# main.net
KiCad netlist of a schematic drawn in Altium Designer
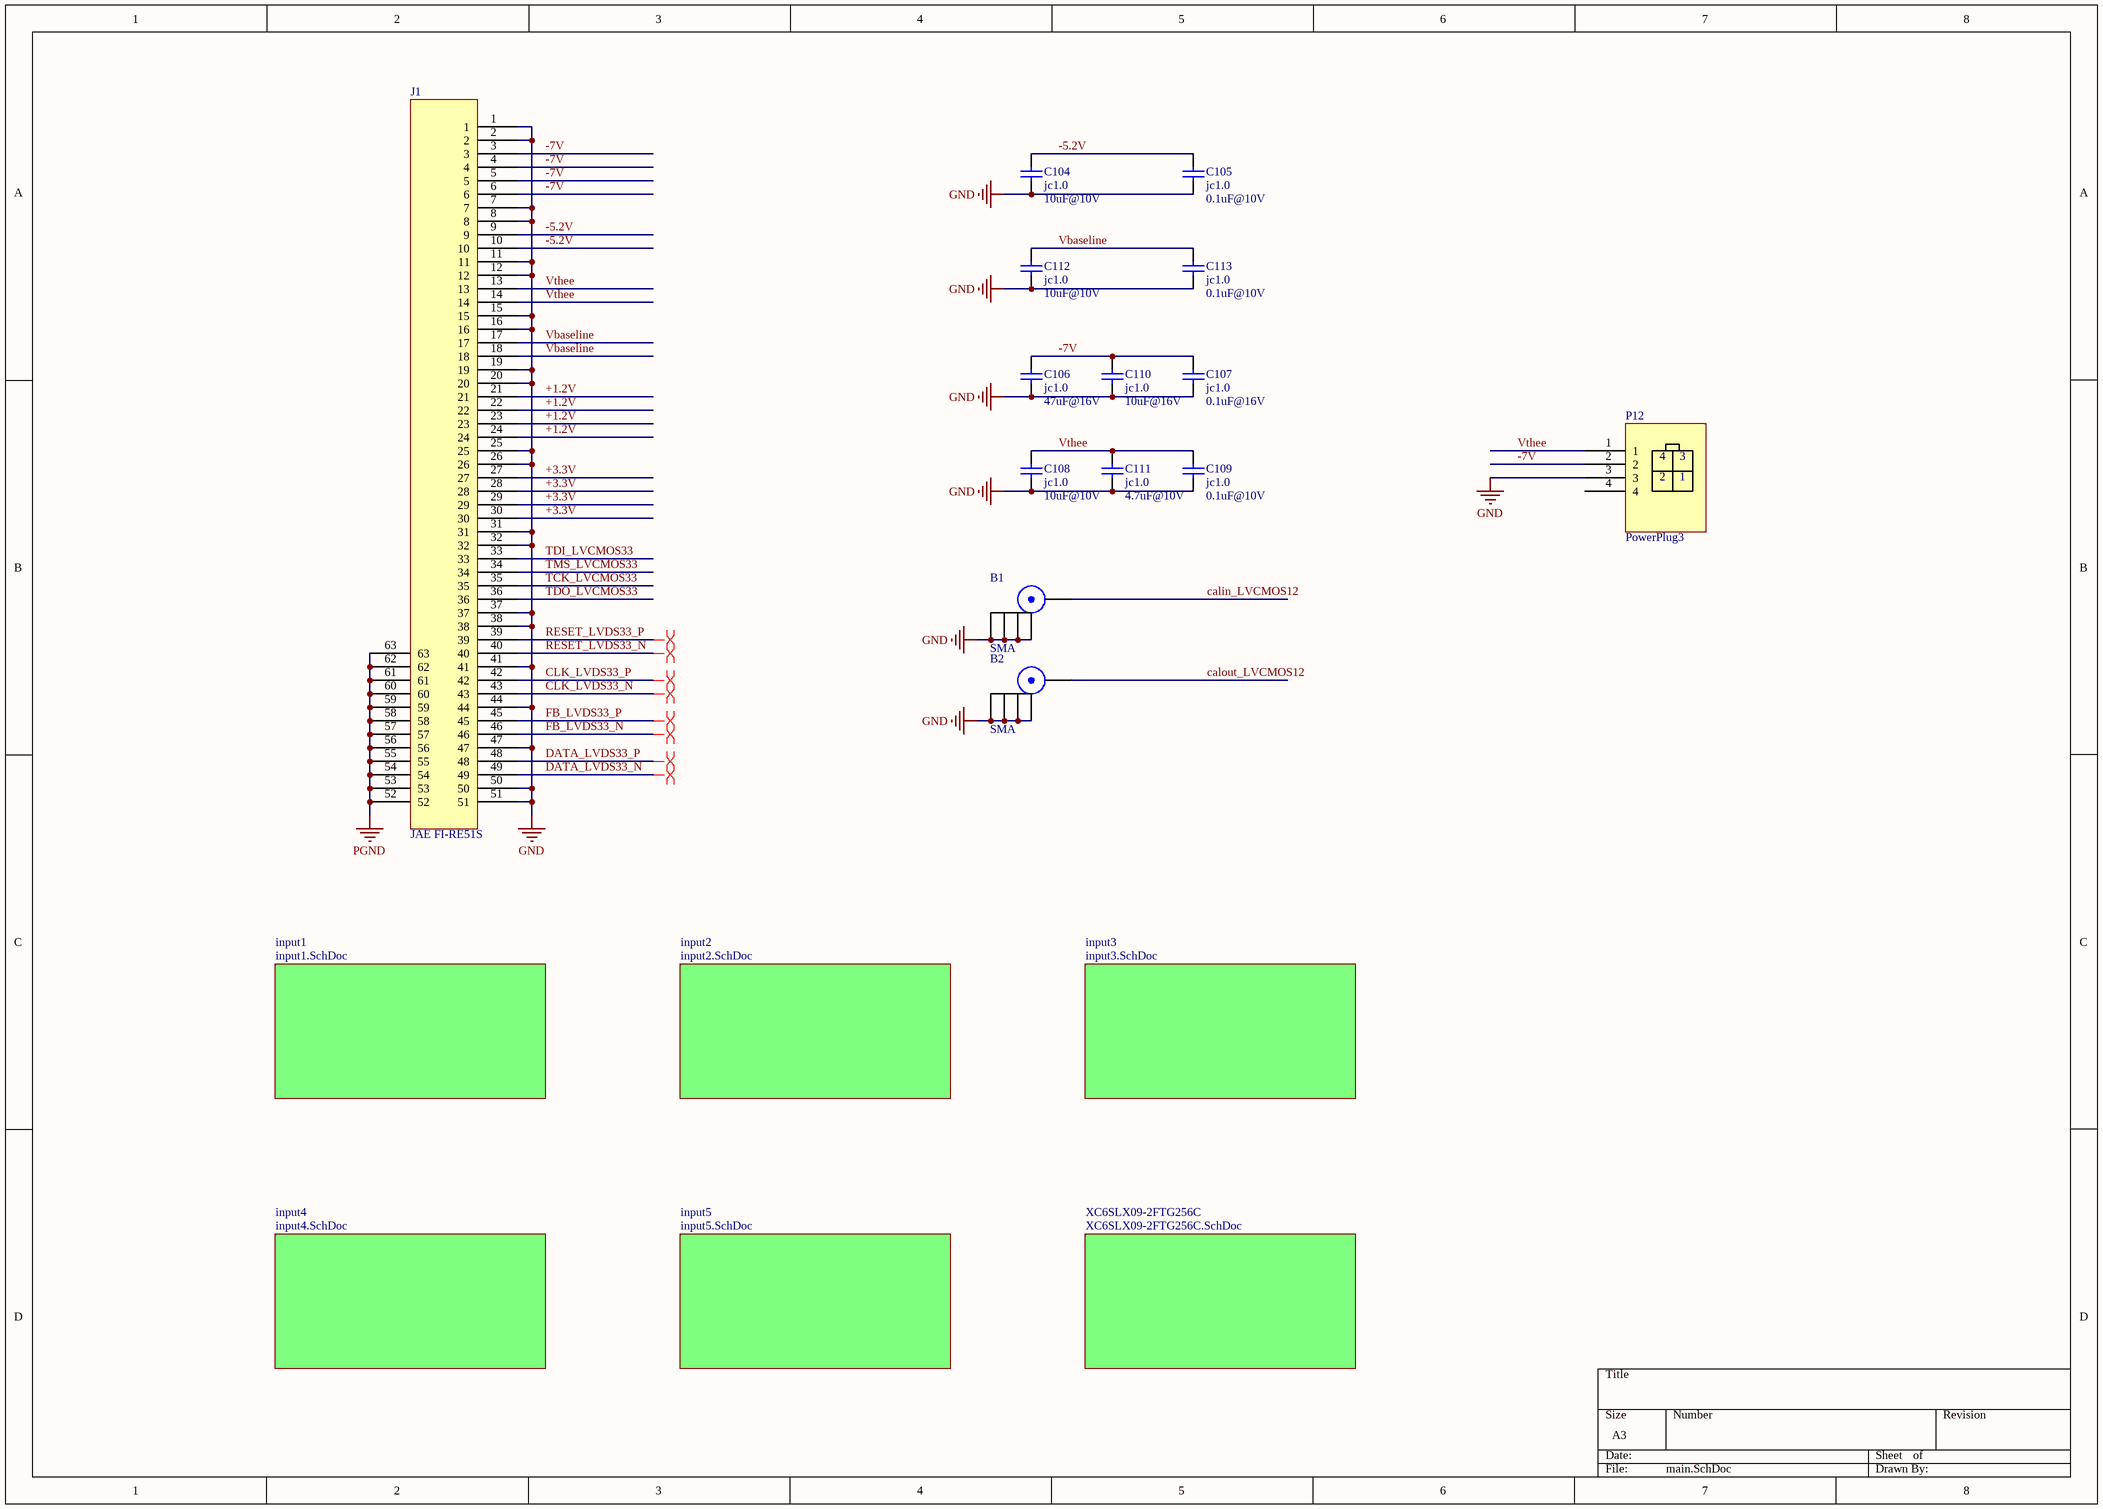
[diagram p0: main.SchDoc]

(export (version "E")
  (design (tool "Eeschema 10.0.6"))
  (components
    (comp (ref "B1") (value "SMA") (footprint "SMA_2") (libsource (lib "LIB01DXP2006SchLib") (part "SMA")))
    (comp (ref "B2") (value "SMA") (footprint "SMA_2") (libsource (lib "LIB01DXP2006SchLib") (part "SMA")))
    (comp (ref "C104")
      (value "jc1.0")
      (footprint "0805")
      (description "Capacitor")
      (fields (field (name "ALTIUM_VALUE") "10uF@10V") (field (name "PUBLISHER") "Altium Limited"))
      (libsource (lib "LIB01DXP2006SchLib") (part "Cap"))
    )
    (comp (ref "C105")
      (value "jc1.0")
      (footprint "0805")
      (description "Capacitor")
      (fields (field (name "ALTIUM_VALUE") "0.1uF@10V") (field (name "PUBLISHER") "Altium Limited"))
      (libsource (lib "LIB01DXP2006SchLib") (part "Cap"))
    )
    (comp (ref "C106")
      (value "jc1.0")
      (footprint "1210")
      (description "Capacitor")
      (fields (field (name "ALTIUM_VALUE") "47uF@16V") (field (name "PUBLISHER") "Altium Limited"))
      (libsource (lib "LIB01DXP2006SchLib") (part "Cap"))
    )
    (comp (ref "C107")
      (value "jc1.0")
      (footprint "0805")
      (description "Capacitor")
      (fields (field (name "ALTIUM_VALUE") "0.1uF@16V") (field (name "PUBLISHER") "Altium Limited"))
      (libsource (lib "LIB01DXP2006SchLib") (part "Cap"))
    )
    (comp (ref "C108")
      (value "jc1.0")
      (footprint "0805")
      (description "Capacitor")
      (fields (field (name "ALTIUM_VALUE") "10uF@10V") (field (name "PUBLISHER") "Altium Limited"))
      (libsource (lib "LIB01DXP2006SchLib") (part "Cap"))
    )
    (comp (ref "C109")
      (value "jc1.0")
      (footprint "0805")
      (description "Capacitor")
      (fields (field (name "ALTIUM_VALUE") "0.1uF@10V") (field (name "PUBLISHER") "Altium Limited"))
      (libsource (lib "LIB01DXP2006SchLib") (part "Cap"))
    )
    (comp (ref "C110")
      (value "jc1.0")
      (footprint "0805")
      (description "Capacitor")
      (fields (field (name "ALTIUM_VALUE") "10uF@16V") (field (name "PUBLISHER") "Altium Limited"))
      (libsource (lib "LIB01DXP2006SchLib") (part "Cap"))
    )
    (comp (ref "C111")
      (value "jc1.0")
      (footprint "0805")
      (description "Capacitor")
      (fields (field (name "ALTIUM_VALUE") "4.7uF@10V") (field (name "PUBLISHER") "Altium Limited"))
      (libsource (lib "LIB01DXP2006SchLib") (part "Cap"))
    )
    (comp (ref "C112")
      (value "jc1.0")
      (footprint "0805")
      (description "Capacitor")
      (fields (field (name "ALTIUM_VALUE") "10uF@10V") (field (name "PUBLISHER") "Altium Limited"))
      (libsource (lib "LIB01DXP2006SchLib") (part "Cap"))
    )
    (comp (ref "C113")
      (value "jc1.0")
      (footprint "0805")
      (description "Capacitor")
      (fields (field (name "ALTIUM_VALUE") "0.1uF@10V") (field (name "PUBLISHER") "Altium Limited"))
      (libsource (lib "LIB01DXP2006SchLib") (part "Cap"))
    )
    (comp (ref "J1")
      (value "JAE FI-RE51S")
      (footprint "FI-RE51S-HF")
      (libsource (lib "LIB01DXP2006SchLib") (part "JAE FI-RE51S"))
    )
    (comp (ref "P12")
      (value "PowerPlug3")
      (footprint "powerplug4")
      (libsource (lib "LIB01DXP2006SchLib") (part "PowerPlug4"))
    )
  )
  (nets
    (net (code "1") (name "/+1.2V") (class "Default")
      (node (ref "J1") (pin "21") (pinfunction "21_21") (pintype "passive"))
      (node (ref "J1") (pin "22") (pinfunction "22_22") (pintype "passive"))
      (node (ref "J1") (pin "23") (pinfunction "23_23") (pintype "passive"))
      (node (ref "J1") (pin "24") (pinfunction "24_24") (pintype "passive"))
    )
    (net (code "2") (name "/+3.3V") (class "Default")
      (node (ref "J1") (pin "27") (pinfunction "27_27") (pintype "passive"))
      (node (ref "J1") (pin "28") (pinfunction "28_28") (pintype "passive"))
      (node (ref "J1") (pin "29") (pinfunction "29_29") (pintype "passive"))
      (node (ref "J1") (pin "30") (pinfunction "30_30") (pintype "passive"))
    )
    (net (code "3") (name "/-5.2V") (class "Default")
      (node (ref "C104") (pin "2") (pinfunction "2_2") (pintype "passive"))
      (node (ref "C105") (pin "2") (pinfunction "2_2") (pintype "passive"))
      (node (ref "J1") (pin "10") (pinfunction "10_10") (pintype "passive"))
      (node (ref "J1") (pin "9") (pinfunction "9_9") (pintype "passive"))
    )
    (net (code "4") (name "/-7V") (class "Default")
      (node (ref "C106") (pin "2") (pinfunction "2_2") (pintype "passive"))
      (node (ref "C107") (pin "2") (pinfunction "2_2") (pintype "passive"))
      (node (ref "C110") (pin "2") (pinfunction "2_2") (pintype "passive"))
      (node (ref "J1") (pin "3") (pinfunction "3_3") (pintype "passive"))
      (node (ref "J1") (pin "4") (pinfunction "4_4") (pintype "passive"))
      (node (ref "J1") (pin "5") (pinfunction "5_5") (pintype "passive"))
      (node (ref "J1") (pin "6") (pinfunction "6_6") (pintype "passive"))
      (node (ref "P12") (pin "2") (pinfunction "2_2") (pintype "passive"))
    )
    (net (code "5") (name "/CLK_LVDS33_N") (class "Default")
      (node (ref "J1") (pin "43") (pinfunction "43_43") (pintype "passive"))
    )
    (net (code "6") (name "/CLK_LVDS33_P") (class "Default")
      (node (ref "J1") (pin "42") (pinfunction "42_42") (pintype "passive"))
    )
    (net (code "7") (name "/DATA_LVDS33_N") (class "Default")
      (node (ref "J1") (pin "49") (pinfunction "49_49") (pintype "passive"))
    )
    (net (code "8") (name "/DATA_LVDS33_P") (class "Default")
      (node (ref "J1") (pin "48") (pinfunction "48_48") (pintype "passive"))
    )
    (net (code "9") (name "/FB_LVDS33_N") (class "Default")
      (node (ref "J1") (pin "46") (pinfunction "46_46") (pintype "passive"))
    )
    (net (code "10") (name "/FB_LVDS33_P") (class "Default")
      (node (ref "J1") (pin "45") (pinfunction "45_45") (pintype "passive"))
    )
    (net (code "11") (name "/RESET_LVDS33_N") (class "Default")
      (node (ref "J1") (pin "40") (pinfunction "40_40") (pintype "passive"))
    )
    (net (code "12") (name "/RESET_LVDS33_P") (class "Default")
      (node (ref "J1") (pin "39") (pinfunction "39_39") (pintype "passive"))
    )
    (net (code "13") (name "/TCK_LVCMOS33") (class "Default")
      (node (ref "J1") (pin "35") (pinfunction "35_35") (pintype "passive"))
    )
    (net (code "14") (name "/TDI_LVCMOS33") (class "Default")
      (node (ref "J1") (pin "33") (pinfunction "33_33") (pintype "passive"))
    )
    (net (code "15") (name "/TDO_LVCMOS33") (class "Default")
      (node (ref "J1") (pin "36") (pinfunction "36_36") (pintype "passive"))
    )
    (net (code "16") (name "/TMS_LVCMOS33") (class "Default")
      (node (ref "J1") (pin "34") (pinfunction "34_34") (pintype "passive"))
    )
    (net (code "17") (name "/Vbaseline") (class "Default")
      (node (ref "C112") (pin "2") (pinfunction "2_2") (pintype "passive"))
      (node (ref "C113") (pin "2") (pinfunction "2_2") (pintype "passive"))
      (node (ref "J1") (pin "17") (pinfunction "17_17") (pintype "passive"))
      (node (ref "J1") (pin "18") (pinfunction "18_18") (pintype "passive"))
    )
    (net (code "18") (name "/Vthee") (class "Default")
      (node (ref "C108") (pin "2") (pinfunction "2_2") (pintype "passive"))
      (node (ref "C109") (pin "2") (pinfunction "2_2") (pintype "passive"))
      (node (ref "C111") (pin "2") (pinfunction "2_2") (pintype "passive"))
      (node (ref "J1") (pin "13") (pinfunction "13_13") (pintype "passive"))
      (node (ref "J1") (pin "14") (pinfunction "14_14") (pintype "passive"))
      (node (ref "P12") (pin "1") (pinfunction "1_1") (pintype "passive"))
    )
    (net (code "19") (name "/calin_LVCMOS12") (class "Default")
      (node (ref "B1") (pin "1") (pinfunction "X_1") (pintype "passive"))
    )
    (net (code "20") (name "/calout_LVCMOS12") (class "Default")
      (node (ref "B2") (pin "1") (pinfunction "X_1") (pintype "passive"))
    )
    (net (code "21") (name "GND") (class "Default")
      (node (ref "B1") (pin "2") (pinfunction "GND_2") (pintype "passive"))
      (node (ref "B1") (pin "3") (pinfunction "GND_3") (pintype "passive"))
      (node (ref "B1") (pin "4") (pinfunction "GND_4") (pintype "passive"))
      (node (ref "B1") (pin "5") (pinfunction "GND_5") (pintype "passive"))
      (node (ref "B2") (pin "2") (pinfunction "GND_2") (pintype "passive"))
      (node (ref "B2") (pin "3") (pinfunction "GND_3") (pintype "passive"))
      (node (ref "B2") (pin "4") (pinfunction "GND_4") (pintype "passive"))
      (node (ref "B2") (pin "5") (pinfunction "GND_5") (pintype "passive"))
      (node (ref "C104") (pin "1") (pinfunction "1_1") (pintype "passive"))
      (node (ref "C105") (pin "1") (pinfunction "1_1") (pintype "passive"))
      (node (ref "C106") (pin "1") (pinfunction "1_1") (pintype "passive"))
      (node (ref "C107") (pin "1") (pinfunction "1_1") (pintype "passive"))
      (node (ref "C108") (pin "1") (pinfunction "1_1") (pintype "passive"))
      (node (ref "C109") (pin "1") (pinfunction "1_1") (pintype "passive"))
      (node (ref "C110") (pin "1") (pinfunction "1_1") (pintype "passive"))
      (node (ref "C111") (pin "1") (pinfunction "1_1") (pintype "passive"))
      (node (ref "C112") (pin "1") (pinfunction "1_1") (pintype "passive"))
      (node (ref "C113") (pin "1") (pinfunction "1_1") (pintype "passive"))
      (node (ref "J1") (pin "1") (pinfunction "1_1") (pintype "passive"))
      (node (ref "J1") (pin "11") (pinfunction "11_11") (pintype "passive"))
      (node (ref "J1") (pin "12") (pinfunction "12_12") (pintype "passive"))
      (node (ref "J1") (pin "15") (pinfunction "15_15") (pintype "passive"))
      (node (ref "J1") (pin "16") (pinfunction "16_16") (pintype "passive"))
      (node (ref "J1") (pin "19") (pinfunction "19_19") (pintype "passive"))
      (node (ref "J1") (pin "2") (pinfunction "2_2") (pintype "passive"))
      (node (ref "J1") (pin "20") (pinfunction "20_20") (pintype "passive"))
      (node (ref "J1") (pin "25") (pinfunction "25_25") (pintype "passive"))
      (node (ref "J1") (pin "26") (pinfunction "26_26") (pintype "passive"))
      (node (ref "J1") (pin "31") (pinfunction "31_31") (pintype "passive"))
      (node (ref "J1") (pin "32") (pinfunction "32_32") (pintype "passive"))
      (node (ref "J1") (pin "37") (pinfunction "37_37") (pintype "passive"))
      (node (ref "J1") (pin "38") (pinfunction "38_38") (pintype "passive"))
      (node (ref "J1") (pin "41") (pinfunction "41_41") (pintype "passive"))
      (node (ref "J1") (pin "44") (pinfunction "44_44") (pintype "passive"))
      (node (ref "J1") (pin "47") (pinfunction "47_47") (pintype "passive"))
      (node (ref "J1") (pin "50") (pinfunction "50_50") (pintype "passive"))
      (node (ref "J1") (pin "51") (pinfunction "51_51") (pintype "passive"))
      (node (ref "J1") (pin "7") (pinfunction "7_7") (pintype "passive"))
      (node (ref "J1") (pin "8") (pinfunction "8_8") (pintype "passive"))
      (node (ref "P12") (pin "3") (pinfunction "3_3") (pintype "passive"))
    )
    (net (code "22") (name "PGND") (class "Default")
      (node (ref "J1") (pin "52") (pinfunction "52_52") (pintype "passive"))
      (node (ref "J1") (pin "53") (pinfunction "53_53") (pintype "passive"))
      (node (ref "J1") (pin "54") (pinfunction "54_54") (pintype "passive"))
      (node (ref "J1") (pin "55") (pinfunction "55_55") (pintype "passive"))
      (node (ref "J1") (pin "56") (pinfunction "56_56") (pintype "passive"))
      (node (ref "J1") (pin "57") (pinfunction "57_57") (pintype "passive"))
      (node (ref "J1") (pin "58") (pinfunction "58_58") (pintype "passive"))
      (node (ref "J1") (pin "59") (pinfunction "59_59") (pintype "passive"))
      (node (ref "J1") (pin "60") (pinfunction "60_60") (pintype "passive"))
      (node (ref "J1") (pin "61") (pinfunction "61_61") (pintype "passive"))
      (node (ref "J1") (pin "62") (pinfunction "62_62") (pintype "passive"))
      (node (ref "J1") (pin "63") (pinfunction "63_63") (pintype "passive"))
    )
    (net (code "23") (name "unconnected-(P12-Pad4)") (class "Default")
      (node (ref "P12") (pin "4") (pinfunction "4_4") (pintype "passive"))
    )
  )
)
